# controller.net
KiCad netlist of a schematic drawn in EAGLE
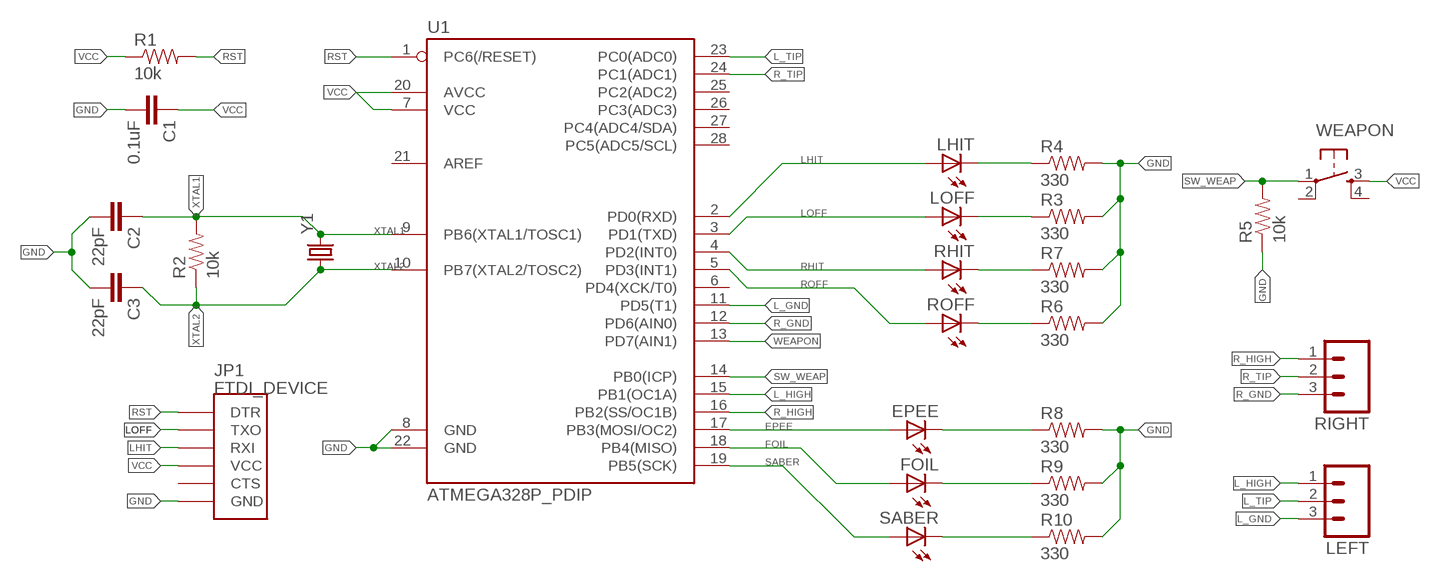
[diagram p0: schematic, sheet 1]

(export (version "E")
  (design (tool "Eeschema 10.0.6"))
  (components
    (comp (ref "C1")
      (value "0.1uF")
      (footprint "eagle-import:CAP-PTH-SMALL-KIT")
      (libsource (lib "eagle-import") (part "CAPKIT"))
    )
    (comp (ref "C2")
      (value "22pF")
      (footprint "eagle-import:CAP-PTH-SMALL-KIT")
      (libsource (lib "eagle-import") (part "CAPKIT"))
    )
    (comp (ref "C3")
      (value "22pF")
      (footprint "eagle-import:CAP-PTH-SMALL-KIT")
      (libsource (lib "eagle-import") (part "CAPKIT"))
    )
    (comp (ref "EPEE")
      (value "LED5MM")
      (footprint "eagle-import:LED5MM")
      (libsource (lib "eagle-import") (part "LED5MM"))
    )
    (comp (ref "FOIL")
      (value "LED5MM")
      (footprint "eagle-import:LED5MM")
      (libsource (lib "eagle-import") (part "LED5MM"))
    )
    (comp (ref "JP1")
      (value "FTDI_DEVICE")
      (footprint "eagle-import:FTDI_DEVICE_SIDE")
      (libsource (lib "eagle-import") (part "FTDI_DEVICE"))
    )
    (comp (ref "LEFT")
      (value "M03LOCK_LONGPADS")
      (footprint "eagle-import:1X03_LOCK_LONGPADS")
      (libsource (lib "eagle-import") (part "M03LOCK_LONGPADS"))
    )
    (comp (ref "LHIT")
      (value "LED5MM")
      (footprint "eagle-import:LED5MM")
      (libsource (lib "eagle-import") (part "LED5MM"))
    )
    (comp (ref "LOFF")
      (value "LED5MM")
      (footprint "eagle-import:LED5MM")
      (libsource (lib "eagle-import") (part "LED5MM"))
    )
    (comp (ref "R1")
      (value "10k")
      (footprint "eagle-import:AXIAL-0.4")
      (libsource (lib "eagle-import") (part "RESISTORPTH-1/4W"))
    )
    (comp (ref "R2")
      (value "10k")
      (footprint "eagle-import:AXIAL-0.4")
      (libsource (lib "eagle-import") (part "RESISTORPTH-1/4W"))
    )
    (comp (ref "R3")
      (value "330")
      (footprint "eagle-import:0603-RES")
      (libsource (lib "eagle-import") (part "RESISTOR0603-RES"))
    )
    (comp (ref "R4")
      (value "330")
      (footprint "eagle-import:0603-RES")
      (libsource (lib "eagle-import") (part "RESISTOR0603-RES"))
    )
    (comp (ref "R5")
      (value "10k")
      (footprint "eagle-import:AXIAL-0.4")
      (libsource (lib "eagle-import") (part "RESISTORPTH-1/4W"))
    )
    (comp (ref "R6")
      (value "330")
      (footprint "eagle-import:0603-RES")
      (libsource (lib "eagle-import") (part "RESISTOR0603-RES"))
    )
    (comp (ref "R7")
      (value "330")
      (footprint "eagle-import:0603-RES")
      (libsource (lib "eagle-import") (part "RESISTOR0603-RES"))
    )
    (comp (ref "R8")
      (value "330")
      (footprint "eagle-import:0603-RES")
      (libsource (lib "eagle-import") (part "RESISTOR0603-RES"))
    )
    (comp (ref "R9")
      (value "330")
      (footprint "eagle-import:0603-RES")
      (libsource (lib "eagle-import") (part "RESISTOR0603-RES"))
    )
    (comp (ref "R10")
      (value "330")
      (footprint "eagle-import:0603-RES")
      (libsource (lib "eagle-import") (part "RESISTOR0603-RES"))
    )
    (comp (ref "RHIT")
      (value "LED5MM")
      (footprint "eagle-import:LED5MM")
      (libsource (lib "eagle-import") (part "LED5MM"))
    )
    (comp (ref "RIGHT")
      (value "M03LOCK_LONGPADS")
      (footprint "eagle-import:1X03_LOCK_LONGPADS")
      (libsource (lib "eagle-import") (part "M03LOCK_LONGPADS"))
    )
    (comp (ref "ROFF")
      (value "LED5MM")
      (footprint "eagle-import:LED5MM")
      (libsource (lib "eagle-import") (part "LED5MM"))
    )
    (comp (ref "SABER")
      (value "LED5MM")
      (footprint "eagle-import:LED5MM")
      (libsource (lib "eagle-import") (part "LED5MM"))
    )
    (comp (ref "U1")
      (value "ATMEGA328P_PDIP")
      (footprint "eagle-import:DIL28-3")
      (libsource (lib "eagle-import") (part "ATMEGA328P_PDIP"))
    )
    (comp (ref "WEAPON")
      (value "TAC_SWITCHPTH")
      (footprint "eagle-import:TACTILE-PTH")
      (libsource (lib "eagle-import") (part "TAC_SWITCHPTH"))
    )
    (comp (ref "Y1")
      (value "CRYSTALHC49US")
      (footprint "eagle-import:HC49US")
      (libsource (lib "eagle-import") (part "CRYSTALHC49US"))
    )
  )
  (nets
    (net (code "1") (name "/EPEE") (class "Default")
      (node (ref "EPEE") (pin "A") (pinfunction "A_A") (pintype "passive"))
      (node (ref "U1") (pin "17") (pinfunction "PB3(MOSI/OC2)_17") (pintype "bidirectional"))
    )
    (net (code "2") (name "/FOIL") (class "Default")
      (node (ref "FOIL") (pin "A") (pinfunction "A_A") (pintype "passive"))
      (node (ref "U1") (pin "18") (pinfunction "PB4(MISO)_18") (pintype "bidirectional"))
    )
    (net (code "3") (name "/RHIT") (class "Default")
      (node (ref "RHIT") (pin "A") (pinfunction "A_A") (pintype "passive"))
      (node (ref "U1") (pin "4") (pinfunction "PD2(INT0)_4") (pintype "bidirectional"))
    )
    (net (code "4") (name "/ROFF") (class "Default")
      (node (ref "ROFF") (pin "A") (pinfunction "A_A") (pintype "passive"))
      (node (ref "U1") (pin "5") (pinfunction "PD3(INT1)_5") (pintype "bidirectional"))
    )
    (net (code "5") (name "/SABER") (class "Default")
      (node (ref "SABER") (pin "A") (pinfunction "A_A") (pintype "passive"))
      (node (ref "U1") (pin "19") (pinfunction "PB5(SCK)_19") (pintype "bidirectional"))
    )
    (net (code "6") (name "GND") (class "Default")
      (node (ref "C1") (pin "2") (pinfunction "2_2") (pintype "passive"))
      (node (ref "C2") (pin "2") (pinfunction "2_2") (pintype "passive"))
      (node (ref "C3") (pin "2") (pinfunction "2_2") (pintype "passive"))
      (node (ref "JP1") (pin "P$6") (pinfunction "GND_P$6") (pintype "bidirectional"))
      (node (ref "R10") (pin "2") (pinfunction "2_2") (pintype "passive"))
      (node (ref "R3") (pin "2") (pinfunction "2_2") (pintype "passive"))
      (node (ref "R4") (pin "2") (pinfunction "2_2") (pintype "passive"))
      (node (ref "R5") (pin "P$1") (pinfunction "1_P$1") (pintype "passive"))
      (node (ref "R6") (pin "2") (pinfunction "2_2") (pintype "passive"))
      (node (ref "R7") (pin "2") (pinfunction "2_2") (pintype "passive"))
      (node (ref "R8") (pin "2") (pinfunction "2_2") (pintype "passive"))
      (node (ref "R9") (pin "2") (pinfunction "2_2") (pintype "passive"))
      (node (ref "U1") (pin "22") (pinfunction "GND_22") (pintype "bidirectional"))
      (node (ref "U1") (pin "8") (pinfunction "GND_8") (pintype "bidirectional"))
    )
    (net (code "7") (name "LHIT") (class "Default")
      (node (ref "JP1") (pin "P$3") (pinfunction "RXI_P$3") (pintype "bidirectional"))
      (node (ref "LHIT") (pin "A") (pinfunction "A_A") (pintype "passive"))
      (node (ref "U1") (pin "2") (pinfunction "PD0(RXD)_2") (pintype "bidirectional"))
    )
    (net (code "8") (name "LOFF") (class "Default")
      (node (ref "JP1") (pin "P$2") (pinfunction "TXO_P$2") (pintype "bidirectional"))
      (node (ref "LOFF") (pin "A") (pinfunction "A_A") (pintype "passive"))
      (node (ref "U1") (pin "3") (pinfunction "PD1(TXD)_3") (pintype "bidirectional"))
    )
    (net (code "9") (name "L_GND") (class "Default")
      (node (ref "LEFT") (pin "3") (pinfunction "3_3") (pintype "passive"))
      (node (ref "U1") (pin "11") (pinfunction "PD5(T1)_11") (pintype "bidirectional"))
    )
    (net (code "10") (name "L_HIGH") (class "Default")
      (node (ref "LEFT") (pin "1") (pinfunction "1_1") (pintype "passive"))
      (node (ref "U1") (pin "15") (pinfunction "PB1(OC1A)_15") (pintype "bidirectional"))
    )
    (net (code "11") (name "L_TIP") (class "Default")
      (node (ref "LEFT") (pin "2") (pinfunction "2_2") (pintype "passive"))
      (node (ref "U1") (pin "23") (pinfunction "PC0(ADC0)_23") (pintype "bidirectional"))
    )
    (net (code "12") (name "Net-(EPEE-C)") (class "Default")
      (node (ref "EPEE") (pin "K") (pinfunction "C_K") (pintype "passive"))
      (node (ref "R8") (pin "1") (pinfunction "1_1") (pintype "passive"))
    )
    (net (code "13") (name "Net-(FOIL-C)") (class "Default")
      (node (ref "FOIL") (pin "K") (pinfunction "C_K") (pintype "passive"))
      (node (ref "R9") (pin "1") (pinfunction "1_1") (pintype "passive"))
    )
    (net (code "14") (name "Net-(LHIT-C)") (class "Default")
      (node (ref "LHIT") (pin "K") (pinfunction "C_K") (pintype "passive"))
      (node (ref "R4") (pin "1") (pinfunction "1_1") (pintype "passive"))
    )
    (net (code "15") (name "Net-(LOFF-C)") (class "Default")
      (node (ref "LOFF") (pin "K") (pinfunction "C_K") (pintype "passive"))
      (node (ref "R3") (pin "1") (pinfunction "1_1") (pintype "passive"))
    )
    (net (code "16") (name "Net-(RHIT-C)") (class "Default")
      (node (ref "R7") (pin "1") (pinfunction "1_1") (pintype "passive"))
      (node (ref "RHIT") (pin "K") (pinfunction "C_K") (pintype "passive"))
    )
    (net (code "17") (name "Net-(ROFF-C)") (class "Default")
      (node (ref "R6") (pin "1") (pinfunction "1_1") (pintype "passive"))
      (node (ref "ROFF") (pin "K") (pinfunction "C_K") (pintype "passive"))
    )
    (net (code "18") (name "Net-(SABER-C)") (class "Default")
      (node (ref "R10") (pin "1") (pinfunction "1_1") (pintype "passive"))
      (node (ref "SABER") (pin "K") (pinfunction "C_K") (pintype "passive"))
    )
    (net (code "19") (name "RST") (class "Default")
      (node (ref "JP1") (pin "P$1") (pinfunction "DTR_P$1") (pintype "bidirectional"))
      (node (ref "R1") (pin "P$2") (pinfunction "2_P$2") (pintype "passive"))
      (node (ref "U1") (pin "1") (pinfunction "PC6(/RESET)_1") (pintype "bidirectional"))
    )
    (net (code "20") (name "R_GND") (class "Default")
      (node (ref "RIGHT") (pin "3") (pinfunction "3_3") (pintype "passive"))
      (node (ref "U1") (pin "12") (pinfunction "PD6(AIN0)_12") (pintype "bidirectional"))
    )
    (net (code "21") (name "R_HIGH") (class "Default")
      (node (ref "RIGHT") (pin "1") (pinfunction "1_1") (pintype "passive"))
      (node (ref "U1") (pin "16") (pinfunction "PB2(SS/OC1B)_16") (pintype "bidirectional"))
    )
    (net (code "22") (name "R_TIP") (class "Default")
      (node (ref "RIGHT") (pin "2") (pinfunction "2_2") (pintype "passive"))
      (node (ref "U1") (pin "24") (pinfunction "PC1(ADC1)_24") (pintype "bidirectional"))
    )
    (net (code "23") (name "SW_WEAP") (class "Default")
      (node (ref "R5") (pin "P$2") (pinfunction "2_P$2") (pintype "passive"))
      (node (ref "U1") (pin "14") (pinfunction "PB0(ICP)_14") (pintype "bidirectional"))
      (node (ref "WEAPON") (pin "1") (pinfunction "1_1") (pintype "passive"))
    )
    (net (code "24") (name "VCC") (class "Default")
      (node (ref "C1") (pin "1") (pinfunction "1_1") (pintype "passive"))
      (node (ref "JP1") (pin "P$4") (pinfunction "VCC_P$4") (pintype "bidirectional"))
      (node (ref "R1") (pin "P$1") (pinfunction "1_P$1") (pintype "passive"))
      (node (ref "U1") (pin "20") (pinfunction "AVCC_20") (pintype "bidirectional"))
      (node (ref "U1") (pin "7") (pinfunction "VCC_7") (pintype "bidirectional"))
      (node (ref "WEAPON") (pin "3") (pinfunction "3_3") (pintype "passive"))
    )
    (net (code "25") (name "WEAPON") (class "Default")
      (node (ref "U1") (pin "13") (pinfunction "PD7(AIN1)_13") (pintype "bidirectional"))
    )
    (net (code "26") (name "XTAL1") (class "Default")
      (node (ref "C2") (pin "1") (pinfunction "1_1") (pintype "passive"))
      (node (ref "R2") (pin "P$2") (pinfunction "2_P$2") (pintype "passive"))
      (node (ref "U1") (pin "9") (pinfunction "PB6(XTAL1/TOSC1)_9") (pintype "bidirectional"))
      (node (ref "Y1") (pin "2") (pinfunction "2_2") (pintype "passive"))
    )
    (net (code "27") (name "XTAL2") (class "Default")
      (node (ref "C3") (pin "1") (pinfunction "1_1") (pintype "passive"))
      (node (ref "R2") (pin "P$1") (pinfunction "1_P$1") (pintype "passive"))
      (node (ref "U1") (pin "10") (pinfunction "PB7(XTAL2/TOSC2)_10") (pintype "bidirectional"))
      (node (ref "Y1") (pin "1") (pinfunction "1_1") (pintype "passive"))
    )
    (net (code "28") (name "unconnected-(JP1-CTS-PadP$5)") (class "Default")
      (node (ref "JP1") (pin "P$5") (pinfunction "CTS_P$5") (pintype "bidirectional"))
    )
    (net (code "29") (name "unconnected-(U1-AREF-Pad21)") (class "Default")
      (node (ref "U1") (pin "21") (pinfunction "AREF_21") (pintype "bidirectional"))
    )
    (net (code "30") (name "unconnected-(U1-PC2(ADC2)-Pad25)") (class "Default")
      (node (ref "U1") (pin "25") (pinfunction "PC2(ADC2)_25") (pintype "bidirectional"))
    )
    (net (code "31") (name "unconnected-(U1-PC3(ADC3)-Pad26)") (class "Default")
      (node (ref "U1") (pin "26") (pinfunction "PC3(ADC3)_26") (pintype "bidirectional"))
    )
    (net (code "32") (name "unconnected-(U1-PC4(ADC4{slash}SDA)-Pad27)") (class "Default")
      (node (ref "U1") (pin "27") (pinfunction "PC4(ADC4/SDA)_27") (pintype "bidirectional"))
    )
    (net (code "33") (name "unconnected-(U1-PC5(ADC5{slash}SCL)-Pad28)") (class "Default")
      (node (ref "U1") (pin "28") (pinfunction "PC5(ADC5/SCL)_28") (pintype "bidirectional"))
    )
    (net (code "34") (name "unconnected-(U1-PD4(XCK{slash}T0)-Pad6)") (class "Default")
      (node (ref "U1") (pin "6") (pinfunction "PD4(XCK/T0)_6") (pintype "bidirectional"))
    )
    (net (code "35") (name "unconnected-(WEAPON-Pad2)") (class "Default")
      (node (ref "WEAPON") (pin "2") (pinfunction "2_2") (pintype "passive"))
    )
    (net (code "36") (name "unconnected-(WEAPON-Pad4)") (class "Default")
      (node (ref "WEAPON") (pin "4") (pinfunction "4_4") (pintype "passive"))
    )
  )
)
